# Laser_Arduino.net
KiCad netlist of a schematic drawn in Altium Designer
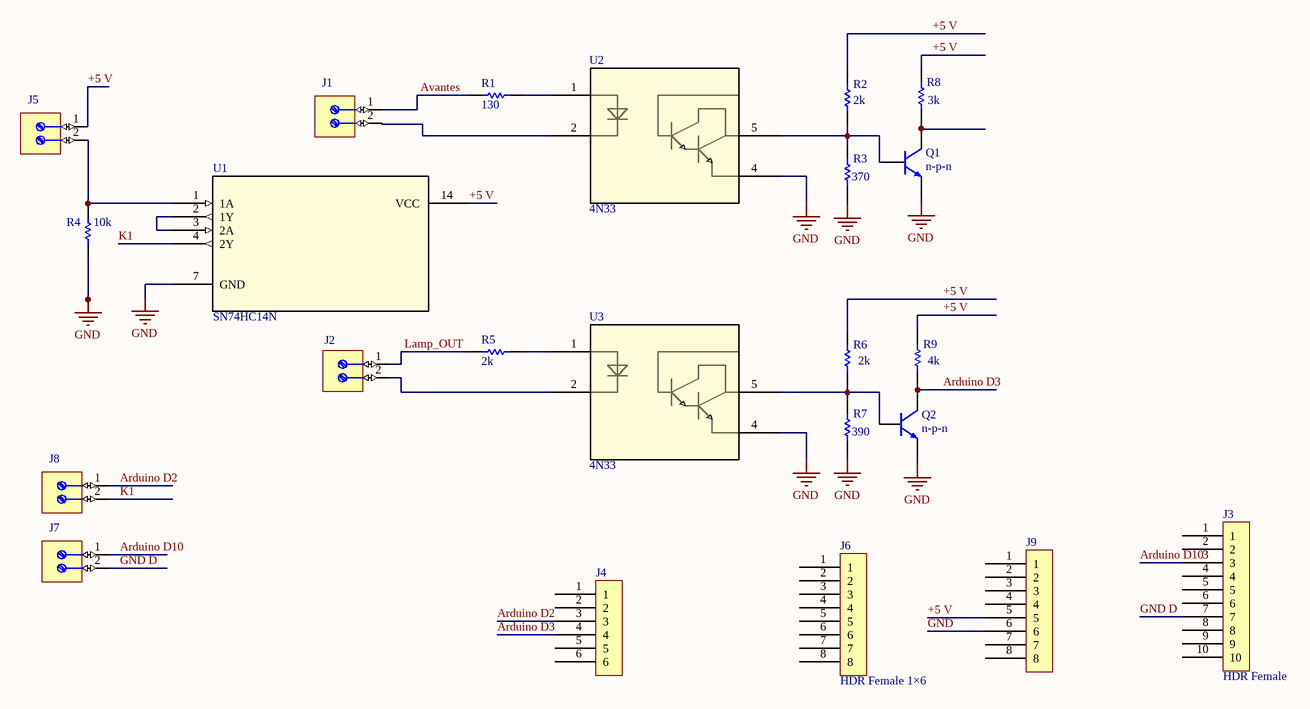
[diagram p0: Laser_Arduino.SchDoc]

(export (version "E")
  (design (tool "Eeschema 10.0.6"))
  (components
    (comp (ref "J1")
      (value "~")
      (footprint "PHOENIX_1715721")
      (description "Connection -POENIX")
      (fields
        (field (name "PART NUMBER") "PHOENIX_1715721")
        (field (name "MANUFACTURER") "PHOENIX CONTACT")
        (field (name "AUTHOR") "CERN DEM JLC")
      )
      (libsource (lib "Laser_Arduino") (part "Connection 2 PIN"))
    )
    (comp (ref "J2")
      (value "~")
      (footprint "PHOENIX_1715721")
      (description "Connection -POENIX")
      (fields
        (field (name "PART NUMBER") "PHOENIX_1715721")
        (field (name "MANUFACTURER") "PHOENIX CONTACT")
        (field (name "AUTHOR") "CERN DEM JLC")
      )
      (libsource (lib "Laser_Arduino") (part "Connection 2 PIN"))
    )
    (comp (ref "J3")
      (value "HDR Female")
      (footprint "Female_Header_10")
      (fields (field (name "MANUFACTURER") "Harwin") (field (name "MANUFACTURER PART NUMBER") "M20-7821046"))
      (libsource (lib "Laser_Arduino") (part "M20-7821046"))
    )
    (comp (ref "J4")
      (value "~")
      (footprint "HDR Female 1Ѓ~8 2.54mm")
      (description "06-WAY SIL VERT SOCKET L/FREE")
      (fields (field (name "MANUFACTURER") "Harwin") (field (name "MANUFACTURER PART NUMBER") "M20-7820646"))
      (libsource (lib "Laser_Arduino") (part "M20-7820646"))
    )
    (comp (ref "J5")
      (value "~")
      (footprint "PHOENIX_1715721")
      (description "Connection -POENIX")
      (fields
        (field (name "PART NUMBER") "PHOENIX_1715721")
        (field (name "MANUFACTURER") "PHOENIX CONTACT")
        (field (name "AUTHOR") "CERN DEM JLC")
      )
      (libsource (lib "Laser_Arduino") (part "Connection 2 PIN"))
    )
    (comp (ref "J6")
      (value "HDR Female 1×6")
      (footprint "HDR Female 1Ѓ~6 2.54mm")
      (description "2.54mm (0.1\") Pitch SIL Vertical PC Tail Socket Assembly, selective gold + tin, 8 contacts")
      (fields (field (name "MANUFACTURER") "Harwin") (field (name "MANUFACTURER PART NUMBER") "M20-7820842"))
      (libsource (lib "Laser_Arduino") (part "M20-7820842"))
    )
    (comp (ref "J7")
      (value "~")
      (footprint "Laser_Arduino:PHOENIX_1715721")
      (description "Connection -POENIX")
      (fields
        (field (name "PART NUMBER") "PHOENIX_1715721")
        (field (name "MANUFACTURER") "PHOENIX CONTACT")
        (field (name "AUTHOR") "CERN DEM JLC")
      )
      (libsource (lib "Laser_Arduino") (part "Connection 2 PIN"))
    )
    (comp (ref "J8")
      (value "~")
      (footprint "Laser_Arduino:PHOENIX_1715721")
      (description "Connection -POENIX")
      (fields
        (field (name "PART NUMBER") "PHOENIX_1715721")
        (field (name "MANUFACTURER") "PHOENIX CONTACT")
        (field (name "AUTHOR") "CERN DEM JLC")
      )
      (libsource (lib "Laser_Arduino") (part "Connection 2 PIN"))
    )
    (comp (ref "J9")
      (value "~")
      (footprint "HDR Female 1Ѓ~8 2.54mm")
      (description "2.54mm (0.1\") Pitch SIL Vertical PC Tail Socket Assembly, selective gold + tin, 8 contacts")
      (fields (field (name "MANUFACTURER") "Harwin") (field (name "MANUFACTURER PART NUMBER") "M20-7820842"))
      (libsource (lib "Laser_Arduino") (part "M20-7820842"))
    )
    (comp (ref "Q1")
      (value "n-p-n")
      (footprint "Laser_Arduino:TO92127P495H695-3")
      (description "Bipolar transistor")
      (libsource (lib "Laser_Arduino") (part "KT417"))
    )
    (comp (ref "Q2")
      (value "n-p-n")
      (footprint "Laser_Arduino:TO92127P495H695-3")
      (description "Bipolar transistor")
      (libsource (lib "Laser_Arduino") (part "KT417"))
    )
    (comp (ref "R1")
      (value "Res1")
      (footprint "STA_RMCF0805_STP-M")
      (description "Chip Resistor")
      (fields
        (field (name "MANUFACTURER") "Panasonic")
        (field (name "MANUFACTURER PART NUMBER") "ERJ-3GEYJ103V")
        (field (name "RESISTANCE") "130")
      )
      (libsource (lib "Laser_Arduino") (part "Res1"))
    )
    (comp (ref "R2")
      (value "Res1")
      (footprint "STA_RMCF0805_STP-M")
      (description "Chip Resistor")
      (fields
        (field (name "MANUFACTURER") "Panasonic")
        (field (name "MANUFACTURER PART NUMBER") "ERJ-3GEYJ103V")
        (field (name "RESISTANCE") "2k")
      )
      (libsource (lib "Laser_Arduino") (part "Res1"))
    )
    (comp (ref "R3")
      (value "Res1")
      (footprint "STA_RMCF0805_STP-M")
      (description "Chip Resistor")
      (fields
        (field (name "MANUFACTURER") "Panasonic")
        (field (name "MANUFACTURER PART NUMBER") "ERJ-3GEYJ103V")
        (field (name "RESISTANCE") "370")
      )
      (libsource (lib "Laser_Arduino") (part "Res1"))
    )
    (comp (ref "R4")
      (value "Res1")
      (footprint "STA_RMCF0805_STP-M")
      (description "Chip Resistor")
      (fields
        (field (name "MANUFACTURER") "Panasonic")
        (field (name "MANUFACTURER PART NUMBER") "ERJ-3GEYJ103V")
        (field (name "RESISTANCE") "10k")
      )
      (libsource (lib "Laser_Arduino") (part "Res1"))
    )
    (comp (ref "R5")
      (value "Res1")
      (footprint "STA_RMCF0805_STP-M")
      (description "Chip Resistor")
      (fields
        (field (name "MANUFACTURER") "Panasonic")
        (field (name "MANUFACTURER PART NUMBER") "ERJ-3GEYJ103V")
        (field (name "RESISTANCE") "2k")
      )
      (libsource (lib "Laser_Arduino") (part "Res1"))
    )
    (comp (ref "R6")
      (value "Res1")
      (footprint "STA_RMCF0805_STP-M")
      (description "Chip Resistor")
      (fields
        (field (name "MANUFACTURER") "Panasonic")
        (field (name "MANUFACTURER PART NUMBER") "ERJ-3GEYJ103V")
        (field (name "RESISTANCE") "2k")
      )
      (libsource (lib "Laser_Arduino") (part "Res1"))
    )
    (comp (ref "R7")
      (value "Res1")
      (footprint "STA_RMCF0805_STP-M")
      (description "Chip Resistor")
      (fields
        (field (name "MANUFACTURER") "Panasonic")
        (field (name "MANUFACTURER PART NUMBER") "ERJ-3GEYJ103V")
        (field (name "RESISTANCE") "390")
      )
      (libsource (lib "Laser_Arduino") (part "Res1"))
    )
    (comp (ref "R8")
      (value "Res1")
      (footprint "STA_RMCF0805_STP-M")
      (description "Chip Resistor")
      (fields
        (field (name "MANUFACTURER") "Panasonic")
        (field (name "MANUFACTURER PART NUMBER") "ERJ-3GEYJ103V")
        (field (name "RESISTANCE") "3k")
      )
      (libsource (lib "Laser_Arduino") (part "Res1"))
    )
    (comp (ref "R9")
      (value "Res1")
      (footprint "Laser_Arduino:STA_RMCF0805_STP-M")
      (description "Chip Resistor")
      (fields
        (field (name "MANUFACTURER") "Panasonic")
        (field (name "MANUFACTURER PART NUMBER") "ERJ-3GEYJ103V")
        (field (name "RESISTANCE") "4k")
      )
      (libsource (lib "Laser_Arduino") (part "Res1"))
    )
    (comp (ref "U1")
      (value "SN74HC14N")
      (footprint "N14")
      (description "No Description Available")
      (fields (field (name "COPYRIGHT") "Copyright (C) 2022 Ultra Librarian. All rights reserved."))
      (libsource (lib "Laser_Arduino") (part "SN74HC14N"))
    )
    (comp (ref "U2")
      (value "4N33")
      (footprint "DIP-6_4N33_VIS")
      (description "No Description Available")
      (fields (field (name "COPYRIGHT") "Copyright (C) 2022 Ultra Librarian. All rights reserved."))
      (libsource (lib "Laser_Arduino") (part "4N33"))
    )
    (comp (ref "U3")
      (value "4N33")
      (footprint "DIP-6_4N33_VIS")
      (description "No Description Available")
      (fields (field (name "COPYRIGHT") "Copyright (C) 2022 Ultra Librarian. All rights reserved."))
      (libsource (lib "Laser_Arduino") (part "4N33"))
    )
  )
  (nets
    (net (code "1") (name "/+5 V") (class "Default")
      (node (ref "J5") (pin "1") (pinfunction "1_1") (pintype "bidirectional"))
      (node (ref "J9") (pin "5") (pinfunction "5_5") (pintype "passive"))
      (node (ref "R2") (pin "2") (pinfunction "2_2") (pintype "passive"))
      (node (ref "R6") (pin "2") (pinfunction "2_2") (pintype "passive"))
      (node (ref "R8") (pin "2") (pinfunction "2_2") (pintype "passive"))
      (node (ref "R9") (pin "2") (pinfunction "2_2") (pintype "passive"))
      (node (ref "U1") (pin "14") (pinfunction "VCC_14") (pintype "power_in"))
    )
    (net (code "2") (name "/Arduino D2") (class "Default")
      (node (ref "J4") (pin "3") (pinfunction "3_3") (pintype "passive"))
      (node (ref "J8") (pin "1") (pinfunction "1_1") (pintype "bidirectional"))
    )
    (net (code "3") (name "/Arduino D3") (class "Default")
      (node (ref "J4") (pin "4") (pinfunction "4_4") (pintype "passive"))
      (node (ref "Q2") (pin "3") (pinfunction "K_3") (pintype "passive"))
      (node (ref "R9") (pin "1") (pinfunction "1_1") (pintype "passive"))
    )
    (net (code "4") (name "/Arduino D10") (class "Default")
      (node (ref "J3") (pin "3") (pinfunction "3_3") (pintype "passive"))
      (node (ref "J7") (pin "1") (pinfunction "1_1") (pintype "bidirectional"))
    )
    (net (code "5") (name "/Avantes") (class "Default")
      (node (ref "J1") (pin "1") (pinfunction "1_1") (pintype "bidirectional"))
      (node (ref "R1") (pin "2") (pinfunction "2_2") (pintype "passive"))
    )
    (net (code "6") (name "/GND D") (class "Default")
      (node (ref "J3") (pin "7") (pinfunction "7_7") (pintype "passive"))
      (node (ref "J7") (pin "2") (pinfunction "2_2") (pintype "bidirectional"))
    )
    (net (code "7") (name "/K1") (class "Default")
      (node (ref "J8") (pin "2") (pinfunction "2_2") (pintype "bidirectional"))
      (node (ref "U1") (pin "4") (pinfunction "2Y_4") (pintype "output"))
    )
    (net (code "8") (name "/Lamp_OUT") (class "Default")
      (node (ref "J2") (pin "1") (pinfunction "1_1") (pintype "bidirectional"))
      (node (ref "R5") (pin "2") (pinfunction "2_2") (pintype "passive"))
    )
    (net (code "9") (name "GND") (class "Default")
      (node (ref "J9") (pin "6") (pinfunction "6_6") (pintype "passive"))
      (node (ref "Q1") (pin "2") (pinfunction "E_2") (pintype "passive"))
      (node (ref "Q2") (pin "2") (pinfunction "E_2") (pintype "passive"))
      (node (ref "R3") (pin "1") (pinfunction "1_1") (pintype "passive"))
      (node (ref "R4") (pin "1") (pinfunction "1_1") (pintype "passive"))
      (node (ref "R7") (pin "1") (pinfunction "1_1") (pintype "passive"))
      (node (ref "U1") (pin "7") (pinfunction "GND_7") (pintype "power_in"))
      (node (ref "U2") (pin "4") (pinfunction "4_4") (pintype "passive"))
      (node (ref "U3") (pin "4") (pinfunction "4_4") (pintype "passive"))
    )
    (net (code "10") (name "Net-(J1-Pad2)") (class "Default")
      (node (ref "J1") (pin "2") (pinfunction "2_2") (pintype "bidirectional"))
      (node (ref "U2") (pin "2") (pinfunction "C_2") (pintype "passive"))
    )
    (net (code "11") (name "Net-(J2-Pad2)") (class "Default")
      (node (ref "J2") (pin "2") (pinfunction "2_2") (pintype "bidirectional"))
      (node (ref "U3") (pin "2") (pinfunction "C_2") (pintype "passive"))
    )
    (net (code "12") (name "Net-(Q1-B)") (class "Default")
      (node (ref "Q1") (pin "1") (pinfunction "B_1") (pintype "passive"))
      (node (ref "R2") (pin "1") (pinfunction "1_1") (pintype "passive"))
      (node (ref "R3") (pin "2") (pinfunction "2_2") (pintype "passive"))
      (node (ref "U2") (pin "5") (pinfunction "C_5") (pintype "passive"))
    )
    (net (code "13") (name "Net-(Q1-K)") (class "Default")
      (node (ref "Q1") (pin "3") (pinfunction "K_3") (pintype "passive"))
      (node (ref "R8") (pin "1") (pinfunction "1_1") (pintype "passive"))
    )
    (net (code "14") (name "Net-(Q2-B)") (class "Default")
      (node (ref "Q2") (pin "1") (pinfunction "B_1") (pintype "passive"))
      (node (ref "R6") (pin "1") (pinfunction "1_1") (pintype "passive"))
      (node (ref "R7") (pin "2") (pinfunction "2_2") (pintype "passive"))
      (node (ref "U3") (pin "5") (pinfunction "C_5") (pintype "passive"))
    )
    (net (code "15") (name "Net-(U1-1A)") (class "Default")
      (node (ref "J5") (pin "2") (pinfunction "2_2") (pintype "bidirectional"))
      (node (ref "R4") (pin "2") (pinfunction "2_2") (pintype "passive"))
      (node (ref "U1") (pin "1") (pinfunction "1A_1") (pintype "input"))
    )
    (net (code "16") (name "Net-(U1-1Y)") (class "Default")
      (node (ref "U1") (pin "2") (pinfunction "1Y_2") (pintype "output"))
      (node (ref "U1") (pin "3") (pinfunction "2A_3") (pintype "input"))
    )
    (net (code "17") (name "Net-(U2-A)") (class "Default")
      (node (ref "R1") (pin "1") (pinfunction "1_1") (pintype "passive"))
      (node (ref "U2") (pin "1") (pinfunction "A_1") (pintype "passive"))
    )
    (net (code "18") (name "Net-(U3-A)") (class "Default")
      (node (ref "R5") (pin "1") (pinfunction "1_1") (pintype "passive"))
      (node (ref "U3") (pin "1") (pinfunction "A_1") (pintype "passive"))
    )
    (net (code "19") (name "unconnected-(J3-Pad1)") (class "Default")
      (node (ref "J3") (pin "1") (pinfunction "1_1") (pintype "passive"))
    )
    (net (code "20") (name "unconnected-(J3-Pad2)") (class "Default")
      (node (ref "J3") (pin "2") (pinfunction "2_2") (pintype "passive"))
    )
    (net (code "21") (name "unconnected-(J3-Pad4)") (class "Default")
      (node (ref "J3") (pin "4") (pinfunction "4_4") (pintype "passive"))
    )
    (net (code "22") (name "unconnected-(J3-Pad5)") (class "Default")
      (node (ref "J3") (pin "5") (pinfunction "5_5") (pintype "passive"))
    )
    (net (code "23") (name "unconnected-(J3-Pad6)") (class "Default")
      (node (ref "J3") (pin "6") (pinfunction "6_6") (pintype "passive"))
    )
    (net (code "24") (name "unconnected-(J3-Pad8)") (class "Default")
      (node (ref "J3") (pin "8") (pinfunction "8_8") (pintype "passive"))
    )
    (net (code "25") (name "unconnected-(J3-Pad9)") (class "Default")
      (node (ref "J3") (pin "9") (pinfunction "9_9") (pintype "passive"))
    )
    (net (code "26") (name "unconnected-(J3-Pad10)") (class "Default")
      (node (ref "J3") (pin "10") (pinfunction "10_10") (pintype "passive"))
    )
    (net (code "27") (name "unconnected-(J4-Pad1)") (class "Default")
      (node (ref "J4") (pin "1") (pinfunction "1_1") (pintype "passive"))
    )
    (net (code "28") (name "unconnected-(J4-Pad2)") (class "Default")
      (node (ref "J4") (pin "2") (pinfunction "2_2") (pintype "passive"))
    )
    (net (code "29") (name "unconnected-(J4-Pad5)") (class "Default")
      (node (ref "J4") (pin "5") (pinfunction "5_5") (pintype "passive"))
    )
    (net (code "30") (name "unconnected-(J4-Pad6)") (class "Default")
      (node (ref "J4") (pin "6") (pinfunction "6_6") (pintype "passive"))
    )
    (net (code "31") (name "unconnected-(J6-Pad1)") (class "Default")
      (node (ref "J6") (pin "1") (pinfunction "1_1") (pintype "passive"))
    )
    (net (code "32") (name "unconnected-(J6-Pad2)") (class "Default")
      (node (ref "J6") (pin "2") (pinfunction "2_2") (pintype "passive"))
    )
    (net (code "33") (name "unconnected-(J6-Pad3)") (class "Default")
      (node (ref "J6") (pin "3") (pinfunction "3_3") (pintype "passive"))
    )
    (net (code "34") (name "unconnected-(J6-Pad4)") (class "Default")
      (node (ref "J6") (pin "4") (pinfunction "4_4") (pintype "passive"))
    )
    (net (code "35") (name "unconnected-(J6-Pad5)") (class "Default")
      (node (ref "J6") (pin "5") (pinfunction "5_5") (pintype "passive"))
    )
    (net (code "36") (name "unconnected-(J6-Pad6)") (class "Default")
      (node (ref "J6") (pin "6") (pinfunction "6_6") (pintype "passive"))
    )
    (net (code "37") (name "unconnected-(J6-Pad7)") (class "Default")
      (node (ref "J6") (pin "7") (pinfunction "7_7") (pintype "passive"))
    )
    (net (code "38") (name "unconnected-(J6-Pad8)") (class "Default")
      (node (ref "J6") (pin "8") (pinfunction "8_8") (pintype "passive"))
    )
    (net (code "39") (name "unconnected-(J9-Pad1)") (class "Default")
      (node (ref "J9") (pin "1") (pinfunction "1_1") (pintype "passive"))
    )
    (net (code "40") (name "unconnected-(J9-Pad2)") (class "Default")
      (node (ref "J9") (pin "2") (pinfunction "2_2") (pintype "passive"))
    )
    (net (code "41") (name "unconnected-(J9-Pad3)") (class "Default")
      (node (ref "J9") (pin "3") (pinfunction "3_3") (pintype "passive"))
    )
    (net (code "42") (name "unconnected-(J9-Pad4)") (class "Default")
      (node (ref "J9") (pin "4") (pinfunction "4_4") (pintype "passive"))
    )
    (net (code "43") (name "unconnected-(J9-Pad7)") (class "Default")
      (node (ref "J9") (pin "7") (pinfunction "7_7") (pintype "passive"))
    )
    (net (code "44") (name "unconnected-(J9-Pad8)") (class "Default")
      (node (ref "J9") (pin "8") (pinfunction "8_8") (pintype "passive"))
    )
    (net (code "45") (name "unconnected-(U1-3A-Pad5)") (class "Default")
      (node (ref "U1") (pin "5") (pinfunction "3A_5") (pintype "input"))
    )
    (net (code "46") (name "unconnected-(U1-3Y-Pad6)") (class "Default")
      (node (ref "U1") (pin "6") (pinfunction "3Y_6") (pintype "output"))
    )
    (net (code "47") (name "unconnected-(U1-4A-Pad9)") (class "Default")
      (node (ref "U1") (pin "9") (pinfunction "4A_9") (pintype "input"))
    )
    (net (code "48") (name "unconnected-(U1-4Y-Pad8)") (class "Default")
      (node (ref "U1") (pin "8") (pinfunction "4Y_8") (pintype "output"))
    )
    (net (code "49") (name "unconnected-(U1-5A-Pad11)") (class "Default")
      (node (ref "U1") (pin "11") (pinfunction "5A_11") (pintype "input"))
    )
    (net (code "50") (name "unconnected-(U1-5Y-Pad10)") (class "Default")
      (node (ref "U1") (pin "10") (pinfunction "5Y_10") (pintype "output"))
    )
    (net (code "51") (name "unconnected-(U1-6A-Pad13)") (class "Default")
      (node (ref "U1") (pin "13") (pinfunction "6A_13") (pintype "input"))
    )
    (net (code "52") (name "unconnected-(U1-6Y-Pad12)") (class "Default")
      (node (ref "U1") (pin "12") (pinfunction "6Y_12") (pintype "output"))
    )
    (net (code "53") (name "unconnected-(U2-B-Pad6)") (class "Default")
      (node (ref "U2") (pin "6") (pinfunction "B_6") (pintype "passive"))
    )
    (net (code "54") (name "unconnected-(U2-NC-Pad3)") (class "Default")
      (node (ref "U2") (pin "3") (pinfunction "NC_3") (pintype "passive"))
    )
    (net (code "55") (name "unconnected-(U3-B-Pad6)") (class "Default")
      (node (ref "U3") (pin "6") (pinfunction "B_6") (pintype "passive"))
    )
    (net (code "56") (name "unconnected-(U3-NC-Pad3)") (class "Default")
      (node (ref "U3") (pin "3") (pinfunction "NC_3") (pintype "passive"))
    )
  )
)
